# Pyr0-Piezo_Direct_Extruder_Board2_1_2.net
KiCad netlist of a schematic drawn in EAGLE
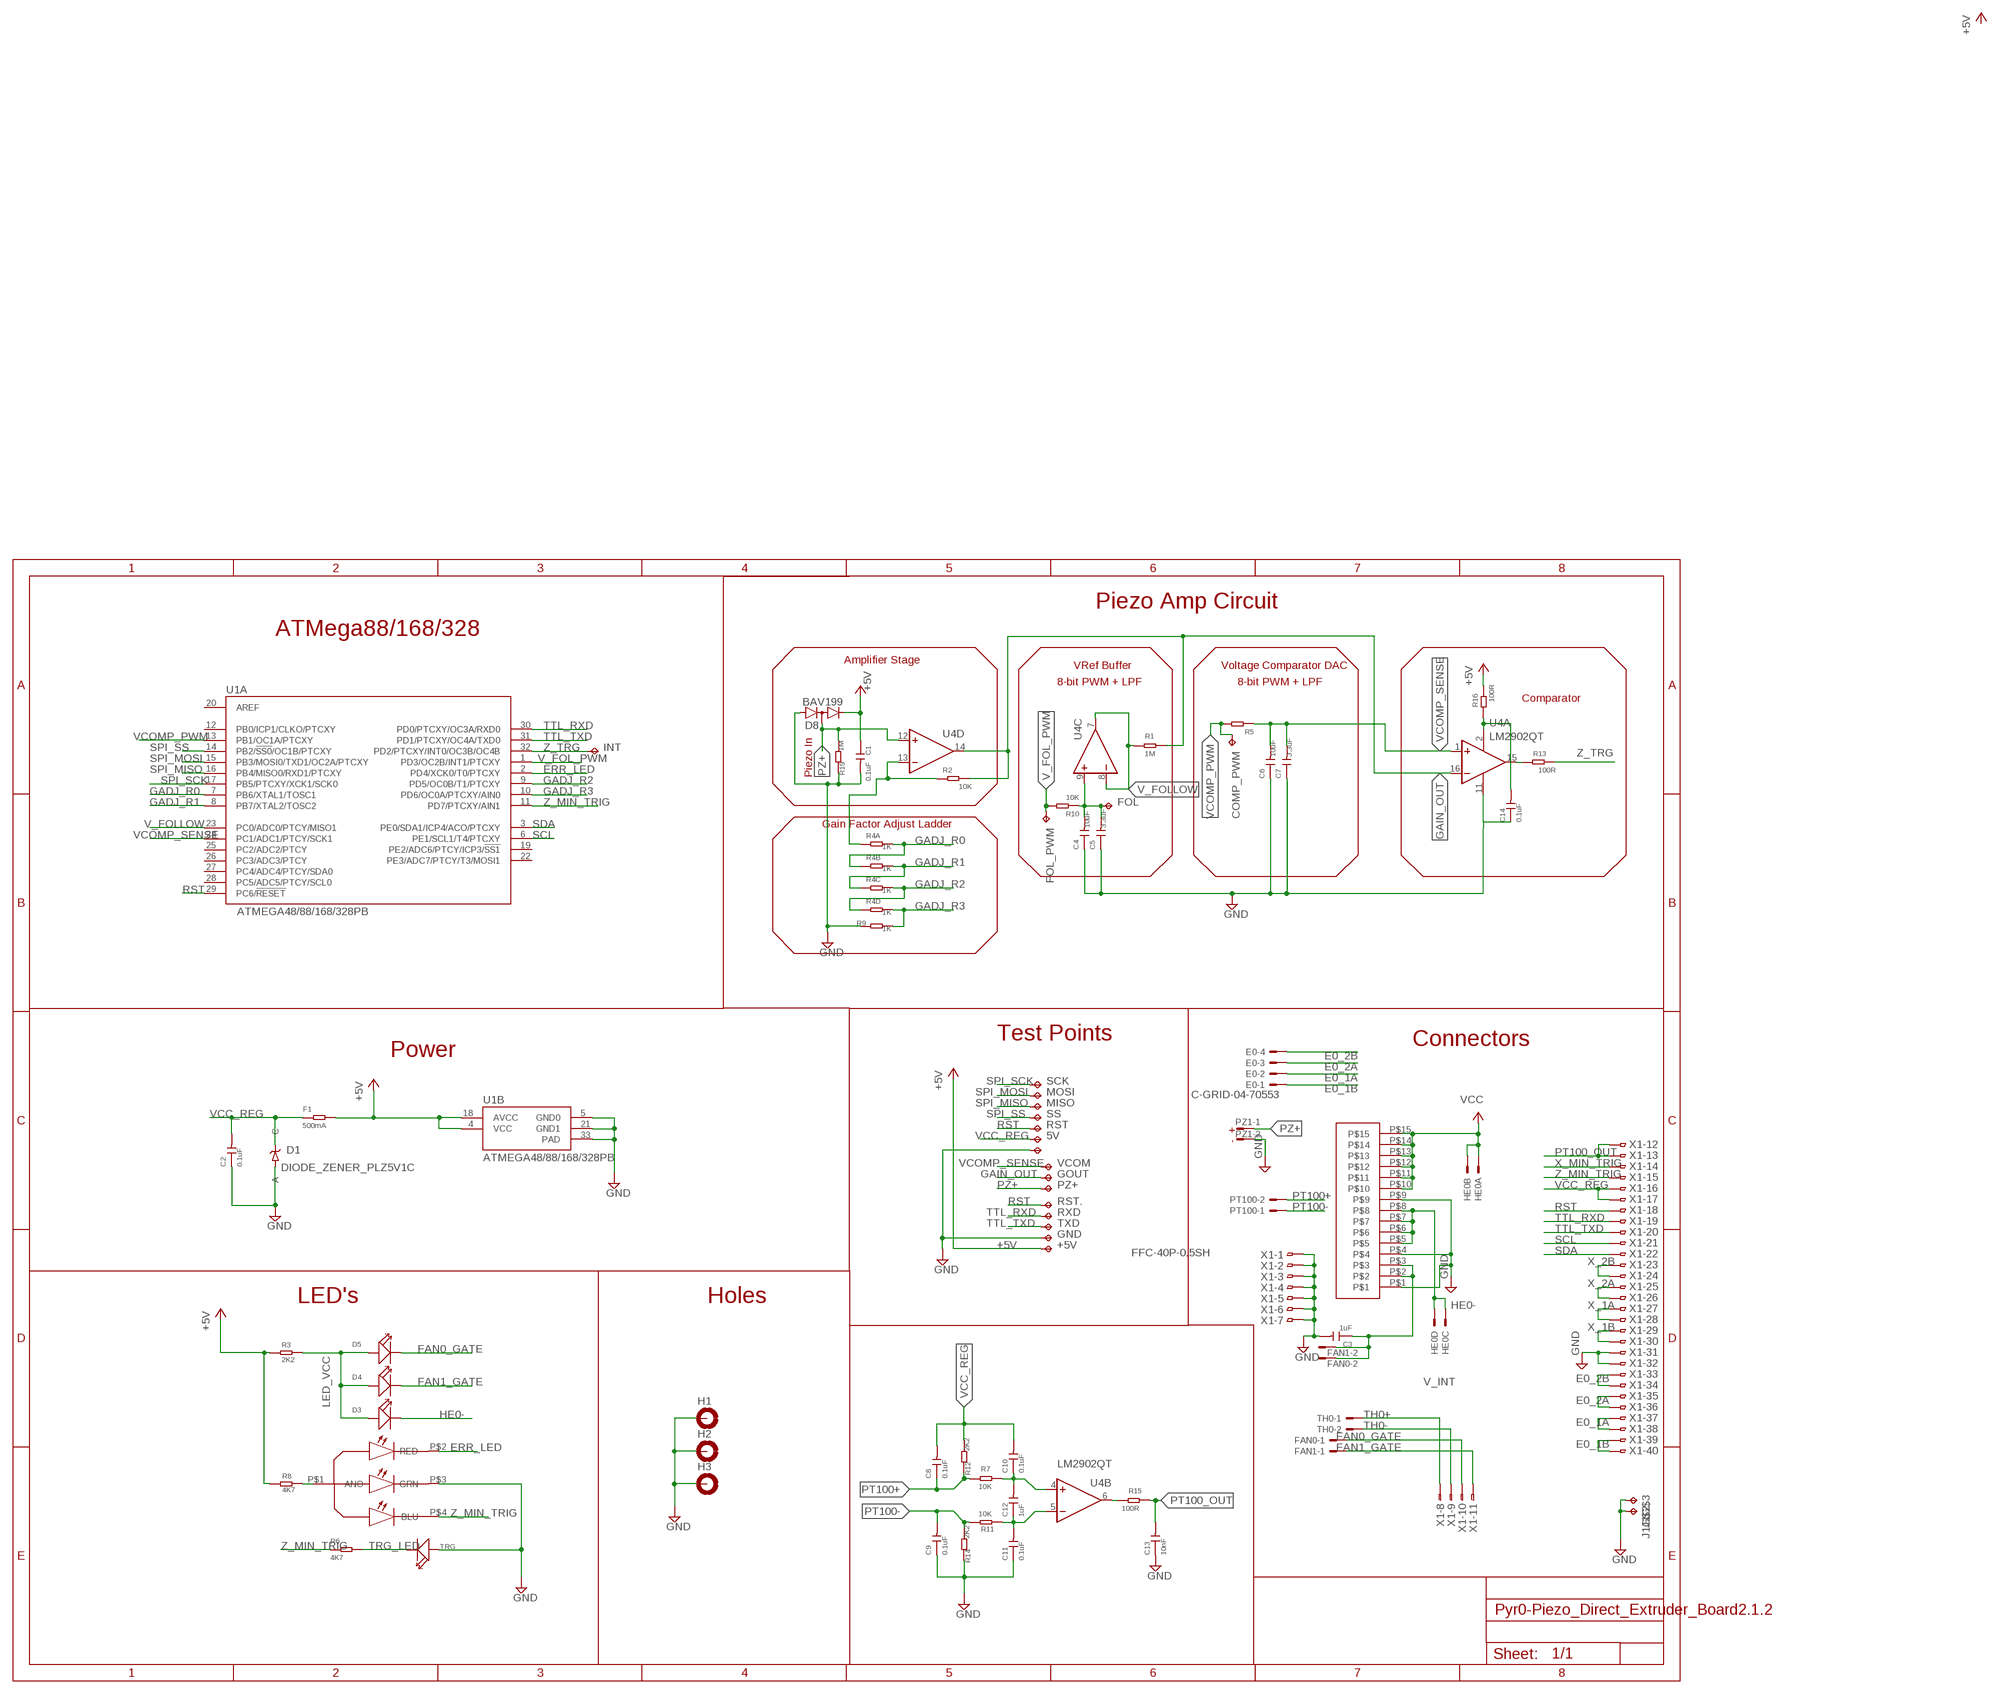
[diagram p0: schematic, sheet 1]

(export (version "E")
  (design (tool "Eeschema 10.0.6"))
  (components
    (comp (ref "+5V")
      (value "TPTP13SQ")
      (footprint "eagle-import:TP13SQ")
      (libsource (lib "eagle-import") (part "testpad_385_TPTP13SQ"))
    )
    (comp (ref "5V")
      (value "TPTP13SQ")
      (footprint "eagle-import:TP13SQ")
      (libsource (lib "eagle-import") (part "TPTP13SQ"))
    )
    (comp (ref "C1")
      (value "0.1uF")
      (footprint "eagle-import:CAPC2012X130")
      (libsource (lib "eagle-import") (part "SEEED-CAPACITOR_CERAMIC-10UF-25V-10%-X5R(0805)CAP_0805-3D"))
    )
    (comp (ref "C2")
      (value "0.1uF")
      (footprint "eagle-import:CAPC1005X50")
      (libsource (lib "eagle-import") (part "CERAMIC-1NF-50V-10%-X7R(0402)CAP_0402"))
    )
    (comp (ref "C3")
      (value "1uF")
      (footprint "eagle-import:CAPC1609X80")
      (libsource (lib "eagle-import") (part "SEEED-CAPACITOR_CERAMIC-10UF-25V-10%-X5R(0805)CAP_0603_GEN"))
    )
    (comp (ref "C4")
      (value "10uF")
      (footprint "eagle-import:CAPC1005X50")
      (libsource (lib "eagle-import") (part "CERAMIC-1NF-50V-10%-X7R(0402)CAP_0402"))
    )
    (comp (ref "C5")
      (value "3.3uF")
      (footprint "eagle-import:CAPC1609X80")
      (libsource (lib "eagle-import") (part "SEEED-CAPACITOR_CERAMIC-10UF-25V-10%-X5R(0805)CAP_0603_GEN"))
    )
    (comp (ref "C6")
      (value "10uF")
      (footprint "eagle-import:CAPC1005X50")
      (libsource (lib "eagle-import") (part "CERAMIC-1NF-50V-10%-X7R(0402)CAP_0402"))
    )
    (comp (ref "C7")
      (value "3.3uF")
      (footprint "eagle-import:CAPC1609X80")
      (libsource (lib "eagle-import") (part "SEEED-CAPACITOR_CERAMIC-10UF-25V-10%-X5R(0805)CAP_0603_GEN"))
    )
    (comp (ref "C8")
      (value "0.1uF")
      (footprint "eagle-import:CAPC1005X50")
      (libsource (lib "eagle-import") (part "CERAMIC-1NF-50V-10%-X7R(0402)CAP_0402"))
    )
    (comp (ref "C9")
      (value "0.1uF")
      (footprint "eagle-import:CAPC1005X50")
      (libsource (lib "eagle-import") (part "CERAMIC-1NF-50V-10%-X7R(0402)CAP_0402"))
    )
    (comp (ref "C10")
      (value "0.1uF")
      (footprint "eagle-import:CAPC1005X50")
      (libsource (lib "eagle-import") (part "CERAMIC-1NF-50V-10%-X7R(0402)CAP_0402"))
    )
    (comp (ref "C11")
      (value "0.1uF")
      (footprint "eagle-import:CAPC1005X50")
      (libsource (lib "eagle-import") (part "CERAMIC-1NF-50V-10%-X7R(0402)CAP_0402"))
    )
    (comp (ref "C12")
      (value "1uF")
      (footprint "eagle-import:CAPC1005X50")
      (libsource (lib "eagle-import") (part "CERAMIC-1NF-50V-10%-X7R(0402)CAP_0402"))
    )
    (comp (ref "C13")
      (value "10nF")
      (footprint "eagle-import:CAPC1005X50")
      (libsource (lib "eagle-import") (part "CERAMIC-1NF-50V-10%-X7R(0402)CAP_0402"))
    )
    (comp (ref "C14")
      (value "0.1uF")
      (footprint "eagle-import:CAPC1005X50")
      (libsource (lib "eagle-import") (part "CERAMIC-1NF-50V-10%-X7R(0402)CAP_0402"))
    )
    (comp (ref "COMP_PWM")
      (value "TPTP09R")
      (footprint "eagle-import:TP09R")
      (libsource (lib "eagle-import") (part "TPTP09R"))
    )
    (comp (ref "D1")
      (value "DIODE_ZENER_PLZ5V1C")
      (footprint "eagle-import:DO-219AC")
      (libsource (lib "eagle-import") (part "DIODE_ZENER_PLZ5V1C"))
    )
    (comp (ref "D2")
      (value "LED-RGB-COM_ANO4PLCC")
      (footprint "eagle-import:4PLCC")
      (libsource (lib "eagle-import") (part "LED-RGB-COM_ANO4PLCC"))
    )
    (comp (ref "D3")
      (value "SEEED-LED_SMD-LED-CLEAR-BLUE(0603)LED_0603")
      (footprint "eagle-import:SEEED-LED_LED-0603")
      (libsource (lib "eagle-import") (part "SEEED-LED_SMD-LED-CLEAR-BLUE(0603)LED_0603"))
    )
    (comp (ref "D4")
      (value "SEEED-LED_SMD-LED-CLEAR-BLUE(0603)LED_0603")
      (footprint "eagle-import:SEEED-LED_LED-0603")
      (libsource (lib "eagle-import") (part "SEEED-LED_SMD-LED-CLEAR-BLUE(0603)LED_0603"))
    )
    (comp (ref "D5")
      (value "SEEED-LED_SMD-LED-CLEAR-BLUE(0603)LED_0603")
      (footprint "eagle-import:SEEED-LED_LED-0603")
      (libsource (lib "eagle-import") (part "SEEED-LED_SMD-LED-CLEAR-BLUE(0603)LED_0603"))
    )
    (comp (ref "D8")
      (value "BAV199")
      (footprint "eagle-import:SOT23")
      (libsource (lib "eagle-import") (part "BAV199"))
    )
    (comp (ref "E0")
      (value "C-GRID-04-70553")
      (footprint "eagle-import:70553-04")
      (fields (field (name "MF") "MOLEX"))
      (libsource (lib "eagle-import") (part "C-GRID-04-70553"))
    )
    (comp (ref "F1")
      (value "500mA")
      (footprint "eagle-import:SEEED-RESISTOR_R0603")
      (libsource (lib "eagle-import") (part "SEEED-RESISTOR_SMD-RES-1.5K-1%-1/10W(0603)DETAILED_MODEL"))
    )
    (comp (ref "FAN0")
      (value "CON-MOLEX-2P-1.27MM048")
      (footprint "eagle-import:53048-02")
      (fields (field (name "MF") "MOLEX") (field (name "MPN") "53048-0210"))
      (libsource (lib "eagle-import") (part "CON-MOLEX-2P-1.27MM048"))
    )
    (comp (ref "FAN1")
      (value "CON-MOLEX-2P-1.27MM048")
      (footprint "eagle-import:53048-02")
      (fields (field (name "MF") "MOLEX") (field (name "MPN") "53048-0210"))
      (libsource (lib "eagle-import") (part "CON-MOLEX-2P-1.27MM048"))
    )
    (comp (ref "FOL")
      (value "TPTP13SQ")
      (footprint "eagle-import:TP13SQ")
      (libsource (lib "eagle-import") (part "TPTP13SQ"))
    )
    (comp (ref "FOL_PWM")
      (value "TPTP09R")
      (footprint "eagle-import:TP09R")
      (libsource (lib "eagle-import") (part "TPTP09R"))
    )
    (comp (ref "GND")
      (value "TPTP13SQ")
      (footprint "eagle-import:TP13SQ")
      (libsource (lib "eagle-import") (part "testpad_385_TPTP13SQ"))
    )
    (comp (ref "GOUT")
      (value "TPTP13SQ")
      (footprint "eagle-import:TP13SQ")
      (libsource (lib "eagle-import") (part "TPTP13SQ"))
    )
    (comp (ref "H1")
      (value "HOLES_MOUNT-PAD-ROUND3.2")
      (footprint "eagle-import:HOLES_3,2-PAD")
      (libsource (lib "eagle-import") (part "HOLES_MOUNT-PAD-ROUND3.2"))
    )
    (comp (ref "H2")
      (value "HOLES_MOUNT-PAD-ROUND3.2")
      (footprint "eagle-import:HOLES_3,2-PAD")
      (libsource (lib "eagle-import") (part "HOLES_MOUNT-PAD-ROUND3.2"))
    )
    (comp (ref "H3")
      (value "HOLES_MOUNT-PAD-ROUND3.2")
      (footprint "eagle-import:HOLES_3,2-PAD")
      (libsource (lib "eagle-import") (part "HOLES_MOUNT-PAD-ROUND3.2"))
    )
    (comp (ref "HE0")
      (value "JST-2.54-2X2JST-DUPONT-2.54-2X2")
      (footprint "eagle-import:HDRRAR4W64P254_2X2_556X736X556B")
      (libsource (lib "eagle-import") (part "JST-2.54-2X2JST-DUPONT-2.54-2X2"))
    )
    (comp (ref "INT")
      (value "TPTP13R")
      (footprint "eagle-import:TP13R")
      (libsource (lib "eagle-import") (part "TPTP13R"))
    )
    (comp (ref "J1")
      (value "FFC-15P-1MM")
      (footprint "eagle-import:FFC-15P-1MM")
      (libsource (lib "eagle-import") (part "FFC-15P-1MM"))
    )
    (comp (ref "MISO")
      (value "TPTP13SQ")
      (footprint "eagle-import:TP13SQ")
      (libsource (lib "eagle-import") (part "TPTP13SQ"))
    )
    (comp (ref "MOSI")
      (value "TPTP13SQ")
      (footprint "eagle-import:TP13SQ")
      (libsource (lib "eagle-import") (part "TPTP13SQ"))
    )
    (comp (ref "PT100")
      (value "CON-MOLEX-2P-1.27MM048")
      (footprint "eagle-import:53048-02")
      (fields (field (name "MF") "MOLEX") (field (name "MPN") "53048-0210"))
      (libsource (lib "eagle-import") (part "CON-MOLEX-2P-1.27MM048"))
    )
    (comp (ref "PZ+")
      (value "TPTP13SQ")
      (footprint "eagle-import:TP13SQ")
      (libsource (lib "eagle-import") (part "TPTP13SQ"))
    )
    (comp (ref "PZ1")
      (value "CON-MOLEX-2P-1.27MM048")
      (footprint "eagle-import:53048-02")
      (fields (field (name "MF") "MOLEX") (field (name "MPN") "53048-0210"))
      (libsource (lib "eagle-import") (part "CON-MOLEX-2P-1.27MM048"))
    )
    (comp (ref "R1")
      (value "1M")
      (footprint "eagle-import:R0402")
      (fields (field (name "MPN") "RC0402JR-070RL"))
      (libsource (lib "eagle-import") (part "SMD-RES-0R-5%-1/16W(0402)"))
    )
    (comp (ref "R2")
      (value "10K")
      (footprint "eagle-import:R0402")
      (fields (field (name "MPN") "RC0402JR-070RL"))
      (libsource (lib "eagle-import") (part "SMD-RES-0R-5%-1/16W(0402)"))
    )
    (comp (ref "R3")
      (value "2K2")
      (footprint "eagle-import:R0402")
      (fields (field (name "MPN") "RC0402JR-070RL"))
      (libsource (lib "eagle-import") (part "SMD-RES-0R-5%-1/16W(0402)"))
    )
    (comp (ref "R4")
      (value "1K")
      (footprint "eagle-import:EXBN8V")
      (libsource (lib "eagle-import") (part "RESISTOR_NETWORK_X40804"))
    )
    (comp (ref "R5")
      (value "0R")
      (footprint "eagle-import:R0402")
      (fields (field (name "MPN") "RC0402JR-070RL"))
      (libsource (lib "eagle-import") (part "SMD-RES-0R-5%-1/16W(0402)"))
    )
    (comp (ref "R6")
      (value "4K7")
      (footprint "eagle-import:R0402")
      (fields (field (name "MPN") "RC0402JR-070RL"))
      (libsource (lib "eagle-import") (part "SMD-RES-0R-5%-1/16W(0402)"))
    )
    (comp (ref "R7")
      (value "10K")
      (footprint "eagle-import:R0402")
      (fields (field (name "MPN") "RC0402JR-070RL"))
      (libsource (lib "eagle-import") (part "SMD-RES-0R-5%-1/16W(0402)"))
    )
    (comp (ref "R8")
      (value "4K7")
      (footprint "eagle-import:R0402")
      (fields (field (name "MPN") "RC0402JR-070RL"))
      (libsource (lib "eagle-import") (part "SMD-RES-0R-5%-1/16W(0402)"))
    )
    (comp (ref "R9")
      (value "1K")
      (footprint "eagle-import:R0402")
      (fields (field (name "MPN") "RC0402JR-070RL"))
      (libsource (lib "eagle-import") (part "SMD-RES-0R-5%-1/16W(0402)"))
    )
    (comp (ref "R10")
      (value "10K")
      (footprint "eagle-import:R0402")
      (fields (field (name "MPN") "RC0402JR-070RL"))
      (libsource (lib "eagle-import") (part "SMD-RES-0R-5%-1/16W(0402)"))
    )
    (comp (ref "R11")
      (value "10K")
      (footprint "eagle-import:R0402")
      (fields (field (name "MPN") "RC0402JR-070RL"))
      (libsource (lib "eagle-import") (part "SMD-RES-0R-5%-1/16W(0402)"))
    )
    (comp (ref "R12")
      (value "2K2")
      (footprint "eagle-import:R0402")
      (fields (field (name "MPN") "RC0402JR-070RL"))
      (libsource (lib "eagle-import") (part "SMD-RES-0R-5%-1/16W(0402)"))
    )
    (comp (ref "R13")
      (value "100R")
      (footprint "eagle-import:R0402")
      (fields (field (name "MPN") "RC0402JR-070RL"))
      (libsource (lib "eagle-import") (part "SMD-RES-0R-5%-1/16W(0402)"))
    )
    (comp (ref "R14")
      (value "2K2")
      (footprint "eagle-import:R0402")
      (fields (field (name "MPN") "RC0402JR-070RL"))
      (libsource (lib "eagle-import") (part "SMD-RES-0R-5%-1/16W(0402)"))
    )
    (comp (ref "R15")
      (value "100R")
      (footprint "eagle-import:R0402")
      (fields (field (name "MPN") "RC0402JR-070RL"))
      (libsource (lib "eagle-import") (part "SMD-RES-0R-5%-1/16W(0402)"))
    )
    (comp (ref "R16")
      (value "100R")
      (footprint "eagle-import:R0402")
      (fields (field (name "MPN") "RC0402JR-070RL"))
      (libsource (lib "eagle-import") (part "SMD-RES-0R-5%-1/16W(0402)"))
    )
    (comp (ref "R19")
      (value "1M")
      (footprint "eagle-import:R0402")
      (fields (field (name "MPN") "RC0402JR-070RL"))
      (libsource (lib "eagle-import") (part "SMD-RES-0R-5%-1/16W(0402)"))
    )
    (comp (ref "RST")
      (value "TPTP13SQ")
      (footprint "eagle-import:TP13SQ")
      (libsource (lib "eagle-import") (part "TPTP13SQ"))
    )
    (comp (ref "RST.")
      (value "TPTP13SQ")
      (footprint "eagle-import:TP13SQ")
      (libsource (lib "eagle-import") (part "testpad_385_TPTP13SQ"))
    )
    (comp (ref "RXD")
      (value "TPTP13SQ")
      (footprint "eagle-import:TP13SQ")
      (libsource (lib "eagle-import") (part "testpad_385_TPTP13SQ"))
    )
    (comp (ref "SCK")
      (value "TPTP13SQ")
      (footprint "eagle-import:TP13SQ")
      (libsource (lib "eagle-import") (part "TPTP13SQ"))
    )
    (comp (ref "SS")
      (value "TPTP06R")
      (footprint "eagle-import:TP06R")
      (libsource (lib "eagle-import") (part "testpad_385_TPTP06R"))
    )
    (comp (ref "TH0")
      (value "CON-MOLEX-2P-1.27MM048")
      (footprint "eagle-import:53048-02")
      (fields (field (name "MF") "MOLEX") (field (name "MPN") "53048-0210"))
      (libsource (lib "eagle-import") (part "CON-MOLEX-2P-1.27MM048"))
    )
    (comp (ref "TRG")
      (value "SEEED-LED_SMD-LED-CLEAR-BLUE(0603)LED_0603")
      (footprint "eagle-import:SEEED-LED_LED-0603")
      (libsource (lib "eagle-import") (part "SEEED-LED_SMD-LED-CLEAR-BLUE(0603)LED_0603"))
    )
    (comp (ref "TXD")
      (value "TPTP13SQ")
      (footprint "eagle-import:TP13SQ")
      (libsource (lib "eagle-import") (part "testpad_385_TPTP13SQ"))
    )
    (comp (ref "U1")
      (value "ATMEGA48/88/168/328PB")
      (footprint "eagle-import:QFN50P500X500X90-33N")
      (fields (field (name "MF") "Microchip") (field (name "MP") "ATMEGA328PB-MU"))
      (libsource (lib "eagle-import") (part "ATMEGA48/88/168/328PB"))
    )
    (comp (ref "U4")
      (value "LM2902QT")
      (footprint "eagle-import:QFN16")
      (libsource (lib "eagle-import") (part "LM2902QT"))
    )
    (comp (ref "VCOM")
      (value "TPTP13SQ")
      (footprint "eagle-import:TP13SQ")
      (libsource (lib "eagle-import") (part "TPTP13SQ"))
    )
    (comp (ref "X1")
      (value "FFC-40P-0.5SH")
      (footprint "eagle-import:FH12-40S-0.5SH")
      (fields (field (name "MPN") "FH12-40S-0.5SH(55)"))
      (libsource (lib "eagle-import") (part "FFC-40P-0.5SH"))
    )
    (comp (ref "⏚")
      (value "TPTP13SQ")
      (footprint "eagle-import:TP13SQ")
      (libsource (lib "eagle-import") (part "testpad_385_TPTP13SQ"))
    )
  )
  (nets
    (net (code "1") (name "+5V") (class "Default")
      (node (ref "+5V") (pin "TP") (pinfunction "TP_TP") (pintype "input"))
      (node (ref "C1") (pin "1") (pinfunction "1_1") (pintype "passive"))
      (node (ref "D8") (pin "2") (pinfunction "C_2") (pintype "passive"))
      (node (ref "F1") (pin "2") (pinfunction "2_2") (pintype "passive"))
      (node (ref "R16") (pin "2") (pinfunction "2_2") (pintype "passive"))
      (node (ref "R3") (pin "1") (pinfunction "1_1") (pintype "passive"))
      (node (ref "R8") (pin "1") (pinfunction "1_1") (pintype "passive"))
      (node (ref "U1") (pin "18") (pinfunction "AVCC_18") (pintype "power_in"))
      (node (ref "U1") (pin "4") (pinfunction "VCC_4") (pintype "power_in"))
    )
    (net (code "2") (name "/E0_1A") (class "Default")
      (node (ref "E0") (pin "2") (pinfunction "S_2") (pintype "passive"))
      (node (ref "X1") (pin "37") (pinfunction "1_37") (pintype "passive"))
      (node (ref "X1") (pin "38") (pinfunction "1_38") (pintype "passive"))
    )
    (net (code "3") (name "/E0_1B") (class "Default")
      (node (ref "E0") (pin "1") (pinfunction "S_1") (pintype "passive"))
      (node (ref "X1") (pin "39") (pinfunction "1_39") (pintype "passive"))
      (node (ref "X1") (pin "40") (pinfunction "1_40") (pintype "passive"))
    )
    (net (code "4") (name "/E0_2A") (class "Default")
      (node (ref "E0") (pin "3") (pinfunction "S_3") (pintype "passive"))
      (node (ref "X1") (pin "35") (pinfunction "1_35") (pintype "passive"))
      (node (ref "X1") (pin "36") (pinfunction "1_36") (pintype "passive"))
    )
    (net (code "5") (name "/E0_2B") (class "Default")
      (node (ref "E0") (pin "4") (pinfunction "S_4") (pintype "passive"))
      (node (ref "X1") (pin "33") (pinfunction "1_33") (pintype "passive"))
      (node (ref "X1") (pin "34") (pinfunction "1_34") (pintype "passive"))
    )
    (net (code "6") (name "/ERR_LED") (class "Default")
      (node (ref "D2") (pin "P$2") (pinfunction "RED_P$2") (pintype "bidirectional"))
      (node (ref "U1") (pin "2") (pinfunction "PD4/XCK0/T0/PTCXY_2") (pintype "bidirectional"))
    )
    (net (code "7") (name "/FAN0_GATE") (class "Default")
      (node (ref "D5") (pin "-") (pinfunction "-_-") (pintype "passive"))
      (node (ref "FAN0") (pin "1") (pinfunction "S_1") (pintype "passive"))
      (node (ref "X1") (pin "10") (pinfunction "1_10") (pintype "passive"))
    )
    (net (code "8") (name "/FAN1_GATE") (class "Default")
      (node (ref "D4") (pin "-") (pinfunction "-_-") (pintype "passive"))
      (node (ref "FAN1") (pin "1") (pinfunction "S_1") (pintype "passive"))
      (node (ref "X1") (pin "11") (pinfunction "1_11") (pintype "passive"))
    )
    (net (code "9") (name "/GADJ_R0") (class "Default")
      (node (ref "R4") (pin "2") (pinfunction "1_2") (pintype "passive"))
      (node (ref "R4") (pin "8") (pinfunction "2_8") (pintype "passive"))
      (node (ref "U1") (pin "7") (pinfunction "PB6/XTAL1/TOSC1_7") (pintype "bidirectional"))
    )
    (net (code "10") (name "/GADJ_R1") (class "Default")
      (node (ref "R4") (pin "3") (pinfunction "1_3") (pintype "passive"))
      (node (ref "R4") (pin "7") (pinfunction "2_7") (pintype "passive"))
      (node (ref "U1") (pin "8") (pinfunction "PB7/XTAL2/TOSC2_8") (pintype "bidirectional"))
    )
    (net (code "11") (name "/GADJ_R2") (class "Default")
      (node (ref "R4") (pin "4") (pinfunction "1_4") (pintype "passive"))
      (node (ref "R4") (pin "6") (pinfunction "2_6") (pintype "passive"))
      (node (ref "U1") (pin "9") (pinfunction "PD5/OC0B/T1/PTCXY_9") (pintype "bidirectional"))
    )
    (net (code "12") (name "/GADJ_R3") (class "Default")
      (node (ref "R4") (pin "5") (pinfunction "2_5") (pintype "passive"))
      (node (ref "R9") (pin "2") (pinfunction "2_2") (pintype "passive"))
      (node (ref "U1") (pin "10") (pinfunction "PD6/OC0A/PTCXY/AIN0_10") (pintype "bidirectional"))
    )
    (net (code "13") (name "/HE0-") (class "Default")
      (node (ref "D3") (pin "-") (pinfunction "-_-") (pintype "passive"))
      (node (ref "HE0") (pin "3") (pinfunction "S_3") (pintype "passive"))
      (node (ref "HE0") (pin "4") (pinfunction "S_4") (pintype "passive"))
      (node (ref "J1") (pin "P$5") (pinfunction "P$5_P$5") (pintype "bidirectional"))
      (node (ref "J1") (pin "P$6") (pinfunction "P$6_P$6") (pintype "bidirectional"))
      (node (ref "J1") (pin "P$7") (pinfunction "P$7_P$7") (pintype "bidirectional"))
      (node (ref "J1") (pin "P$8") (pinfunction "P$8_P$8") (pintype "bidirectional"))
    )
    (net (code "14") (name "/LED_VCC") (class "Default")
      (node (ref "D3") (pin "+") (pinfunction "+_+") (pintype "passive"))
      (node (ref "D4") (pin "+") (pinfunction "+_+") (pintype "passive"))
      (node (ref "D5") (pin "+") (pinfunction "+_+") (pintype "passive"))
      (node (ref "R3") (pin "2") (pinfunction "2_2") (pintype "passive"))
    )
    (net (code "15") (name "/RST") (class "Default")
      (node (ref "RST") (pin "TP") (pinfunction "TP_TP") (pintype "input"))
      (node (ref "RST.") (pin "TP") (pinfunction "TP_TP") (pintype "input"))
      (node (ref "U1") (pin "29") (pinfunction "PC6/~{RESET}_29") (pintype "bidirectional"))
      (node (ref "X1") (pin "18") (pinfunction "1_18") (pintype "passive"))
    )
    (net (code "16") (name "/SCL") (class "Default")
      (node (ref "U1") (pin "6") (pinfunction "PE1/SCL1/T4/PTCXY_6") (pintype "bidirectional"))
      (node (ref "X1") (pin "21") (pinfunction "1_21") (pintype "passive"))
    )
    (net (code "17") (name "/SDA") (class "Default")
      (node (ref "U1") (pin "3") (pinfunction "PE0/SDA1/ICP4/ACO/PTCXY_3") (pintype "bidirectional"))
      (node (ref "X1") (pin "22") (pinfunction "1_22") (pintype "passive"))
    )
    (net (code "18") (name "/SPI_MISO") (class "Default")
      (node (ref "MISO") (pin "TP") (pinfunction "TP_TP") (pintype "input"))
      (node (ref "U1") (pin "16") (pinfunction "PB4/MISO0/RXD1/PTCXY_16") (pintype "bidirectional"))
    )
    (net (code "19") (name "/SPI_MOSI") (class "Default")
      (node (ref "MOSI") (pin "TP") (pinfunction "TP_TP") (pintype "input"))
      (node (ref "U1") (pin "15") (pinfunction "PB3/MOSI0/TXD1/OC2A/PTCXY_15") (pintype "bidirectional"))
    )
    (net (code "20") (name "/SPI_SCK") (class "Default")
      (node (ref "SCK") (pin "TP") (pinfunction "TP_TP") (pintype "input"))
      (node (ref "U1") (pin "17") (pinfunction "PB5/PTCXY/XCK1/SCK0_17") (pintype "bidirectional"))
    )
    (net (code "21") (name "/SPI_SS") (class "Default")
      (node (ref "SS") (pin "TP") (pinfunction "TP_TP") (pintype "input"))
      (node (ref "U1") (pin "14") (pinfunction "PB2/~{SS0}/OC1B/PTCXY_14") (pintype "bidirectional"))
    )
    (net (code "22") (name "/TH0+") (class "Default")
      (node (ref "TH0") (pin "1") (pinfunction "S_1") (pintype "passive"))
      (node (ref "X1") (pin "8") (pinfunction "1_8") (pintype "passive"))
    )
    (net (code "23") (name "/TH0-") (class "Default")
      (node (ref "TH0") (pin "2") (pinfunction "S_2") (pintype "passive"))
      (node (ref "X1") (pin "9") (pinfunction "1_9") (pintype "passive"))
    )
    (net (code "24") (name "/TRG_LED") (class "Default")
      (node (ref "R6") (pin "2") (pinfunction "2_2") (pintype "passive"))
      (node (ref "TRG") (pin "-") (pinfunction "-_-") (pintype "passive"))
    )
    (net (code "25") (name "/TTL_RXD") (class "Default")
      (node (ref "RXD") (pin "TP") (pinfunction "TP_TP") (pintype "input"))
      (node (ref "U1") (pin "30") (pinfunction "PD0/PTCXY/OC3A/RXD0_30") (pintype "bidirectional"))
      (node (ref "X1") (pin "19") (pinfunction "1_19") (pintype "passive"))
    )
    (net (code "26") (name "/TTL_TXD") (class "Default")
      (node (ref "TXD") (pin "TP") (pinfunction "TP_TP") (pintype "input"))
      (node (ref "U1") (pin "31") (pinfunction "PD1/PTCXY/OC4A/TXD0_31") (pintype "bidirectional"))
      (node (ref "X1") (pin "20") (pinfunction "1_20") (pintype "passive"))
    )
    (net (code "27") (name "/V_INT") (class "Default")
      (node (ref "C3") (pin "1") (pinfunction "1_1") (pintype "passive"))
      (node (ref "FAN0") (pin "2") (pinfunction "S_2") (pintype "passive"))
      (node (ref "FAN1") (pin "2") (pinfunction "S_2") (pintype "passive"))
      (node (ref "J1") (pin "P$2") (pinfunction "P$2_P$2") (pintype "bidirectional"))
      (node (ref "J1") (pin "P$3") (pinfunction "P$3_P$3") (pintype "bidirectional"))
    )
    (net (code "28") (name "/X_1A") (class "Default")
      (node (ref "X1") (pin "27") (pinfunction "1_27") (pintype "passive"))
      (node (ref "X1") (pin "28") (pinfunction "1_28") (pintype "passive"))
    )
    (net (code "29") (name "/X_1B") (class "Default")
      (node (ref "X1") (pin "29") (pinfunction "1_29") (pintype "passive"))
      (node (ref "X1") (pin "30") (pinfunction "1_30") (pintype "passive"))
    )
    (net (code "30") (name "/X_2A") (class "Default")
      (node (ref "X1") (pin "25") (pinfunction "1_25") (pintype "passive"))
      (node (ref "X1") (pin "26") (pinfunction "1_26") (pintype "passive"))
    )
    (net (code "31") (name "/X_2B") (class "Default")
      (node (ref "X1") (pin "23") (pinfunction "1_23") (pintype "passive"))
      (node (ref "X1") (pin "24") (pinfunction "1_24") (pintype "passive"))
    )
    (net (code "32") (name "/X_MIN_TRIG") (class "Default")
      (node (ref "X1") (pin "14") (pinfunction "1_14") (pintype "passive"))
    )
    (net (code "33") (name "/Z_MIN_TRIG") (class "Default")
      (node (ref "D2") (pin "P$4") (pinfunction "BLU_P$4") (pintype "bidirectional"))
      (node (ref "R6") (pin "1") (pinfunction "1_1") (pintype "passive"))
      (node (ref "U1") (pin "11") (pinfunction "PD7/PTCXY/AIN1_11") (pintype "bidirectional"))
      (node (ref "X1") (pin "15") (pinfunction "1_15") (pintype "passive"))
    )
    (net (code "34") (name "/Z_TRG") (class "Default")
      (node (ref "INT") (pin "TP") (pinfunction "TP_TP") (pintype "input"))
      (node (ref "R13") (pin "2") (pinfunction "2_2") (pintype "passive"))
      (node (ref "U1") (pin "32") (pinfunction "PD2/PTCXY/INT0/OC3B/OC4B_32") (pintype "bidirectional"))
    )
    (net (code "35") (name "GAIN_OUT") (class "Default")
      (node (ref "GOUT") (pin "TP") (pinfunction "TP_TP") (pintype "input"))
      (node (ref "R1") (pin "2") (pinfunction "2_2") (pintype "passive"))
      (node (ref "R2") (pin "2") (pinfunction "2_2") (pintype "passive"))
      (node (ref "U4") (pin "14") (pinfunction "OUT_14") (pintype "output"))
      (node (ref "U4") (pin "16") (pinfunction "-IN_16") (pintype "input"))
    )
    (net (code "36") (name "GND") (class "Default")
      (node (ref "C1") (pin "2") (pinfunction "2_2") (pintype "passive"))
      (node (ref "C11") (pin "1") (pinfunction "1_1") (pintype "passive"))
      (node (ref "C13") (pin "1") (pinfunction "1_1") (pintype "passive"))
      (node (ref "C14") (pin "1") (pinfunction "1_1") (pintype "passive"))
      (node (ref "C2") (pin "1") (pinfunction "1_1") (pintype "passive"))
      (node (ref "C3") (pin "2") (pinfunction "2_2") (pintype "passive"))
      (node (ref "C4") (pin "1") (pinfunction "1_1") (pintype "passive"))
      (node (ref "C5") (pin "1") (pinfunction "1_1") (pintype "passive"))
      (node (ref "C6") (pin "1") (pinfunction "1_1") (pintype "passive"))
      (node (ref "C7") (pin "1") (pinfunction "1_1") (pintype "passive"))
      (node (ref "C9") (pin "1") (pinfunction "1_1") (pintype "passive"))
      (node (ref "D1") (pin "P$1") (pinfunction "A_P$1") (pintype "passive"))
      (node (ref "D2") (pin "P$3") (pinfunction "GRN_P$3") (pintype "bidirectional"))
      (node (ref "D8") (pin "1") (pinfunction "A_1") (pintype "passive"))
      (node (ref "GND") (pin "TP") (pinfunction "TP_TP") (pintype "input"))
      (node (ref "H1") (pin "B3,2") (pinfunction "MOUNT_B3,2") (pintype "passive"))
      (node (ref "H2") (pin "B3,2") (pinfunction "MOUNT_B3,2") (pintype "passive"))
      (node (ref "H3") (pin "B3,2") (pinfunction "MOUNT_B3,2") (pintype "passive"))
      (node (ref "J1") (pin "P$1") (pinfunction "P$1_P$1") (pintype "bidirectional"))
      (node (ref "J1") (pin "P$16") (pinfunction "TP_P$16") (pintype "input"))
      (node (ref "J1") (pin "P$17") (pinfunction "TP_P$17") (pintype "input"))
      (node (ref "J1") (pin "P$4") (pinfunction "P$4_P$4") (pintype "bidirectional"))
      (node (ref "J1") (pin "P$9") (pinfunction "P$9_P$9") (pintype "bidirectional"))
      (node (ref "PZ1") (pin "2") (pinfunction "S_2") (pintype "passive"))
      (node (ref "R14") (pin "1") (pinfunction "1_1") (pintype "passive"))
      (node (ref "R19") (pin "1") (pinfunction "1_1") (pintype "passive"))
      (node (ref "R9") (pin "1") (pinfunction "1_1") (pintype "passive"))
      (node (ref "TRG") (pin "+") (pinfunction "+_+") (pintype "passive"))
      (node (ref "U1") (pin "21") (pinfunction "GND1_21") (pintype "power_in"))
      (node (ref "U1") (pin "33") (pinfunction "PAD_33") (pintype "power_in"))
      (node (ref "U1") (pin "5") (pinfunction "GND0_5") (pintype "power_in"))
      (node (ref "U4") (pin "11") (pinfunction "V-_11") (pintype "power_in"))
      (node (ref "X1") (pin "1") (pinfunction "1_1") (pintype "passive"))
      (node (ref "X1") (pin "2") (pinfunction "1_2") (pintype "passive"))
      (node (ref "X1") (pin "3") (pinfunction "1_3") (pintype "passive"))
      (node (ref "X1") (pin "31") (pinfunction "1_31") (pintype "passive"))
      (node (ref "X1") (pin "32") (pinfunction "1_32") (pintype "passive"))
      (node (ref "X1") (pin "4") (pinfunction "1_4") (pintype "passive"))
      (node (ref "X1") (pin "5") (pinfunction "1_5") (pintype "passive"))
      (node (ref "X1") (pin "6") (pinfunction "1_6") (pintype "passive"))
      (node (ref "X1") (pin "7") (pinfunction "1_7") (pintype "passive"))
      (node (ref "⏚") (pin "TP") (pinfunction "TP_TP") (pintype "input"))
    )
    (net (code "37") (name "Net-(D2-ANO)") (class "Default")
      (node (ref "D2") (pin "P$1") (pinfunction "ANO_P$1") (pintype "bidirectional"))
      (node (ref "R8") (pin "2") (pinfunction "2_2") (pintype "passive"))
    )
    (net (code "38") (name "Net-(U4A-OUT)") (class "Default")
      (node (ref "R13") (pin "1") (pinfunction "1_1") (pintype "passive"))
      (node (ref "U4") (pin "15") (pinfunction "OUT_15") (pintype "output"))
    )
    (net (code "39") (name "Net-(U4B-+IN)") (class "Default")
      (node (ref "C10") (pin "1") (pinfunction "1_1") (pintype "passive"))
      (node (ref "C12") (pin "2") (pinfunction "2_2") (pintype "passive"))
      (node (ref "R7") (pin "1") (pinfunction "1_1") (pintype "passive"))
      (node (ref "U4") (pin "4") (pinfunction "+IN_4") (pintype "input"))
    )
    (net (code "40") (name "Net-(U4B--IN)") (class "Default")
      (node (ref "C11") (pin "2") (pinfunction "2_2") (pintype "passive"))
      (node (ref "C12") (pin "1") (pinfunction "1_1") (pintype "passive"))
      (node (ref "R11") (pin "1") (pinfunction "1_1") (pintype "passive"))
      (node (ref "U4") (pin "5") (pinfunction "-IN_5") (pintype "input"))
    )
    (net (code "41") (name "Net-(U4B-OUT)") (class "Default")
      (node (ref "R15") (pin "2") (pinfunction "2_2") (pintype "passive"))
      (node (ref "U4") (pin "6") (pinfunction "OUT_6") (pintype "output"))
    )
    (net (code "42") (name "Net-(U4C-+IN)") (class "Default")
      (node (ref "C4") (pin "2") (pinfunction "2_2") (pintype "passive"))
      (node (ref "C5") (pin "2") (pinfunction "2_2") (pintype "passive"))
      (node (ref "FOL") (pin "TP") (pinfunction "TP_TP") (pintype "input"))
      (node (ref "R10") (pin "1") (pinfunction "1_1") (pintype "passive"))
      (node (ref "U4") (pin "9") (pinfunction "+IN_9") (pintype "input"))
    )
    (net (code "43") (name "Net-(U4D--IN)") (class "Default")
      (node (ref "R2") (pin "1") (pinfunction "1_1") (pintype "passive"))
      (node (ref "R4") (pin "1") (pinfunction "1_1") (pintype "passive"))
      (node (ref "U4") (pin "13") (pinfunction "-IN_13") (pintype "input"))
    )
    (net (code "44") (name "Net-(U4E-V+)") (class "Default")
      (node (ref "C14") (pin "2") (pinfunction "2_2") (pintype "passive"))
      (node (ref "R16") (pin "1") (pinfunction "1_1") (pintype "passive"))
      (node (ref "U4") (pin "2") (pinfunction "V+_2") (pintype "power_in"))
    )
    (net (code "45") (name "PT100+") (class "Default")
      (node (ref "C8") (pin "1") (pinfunction "1_1") (pintype "passive"))
      (node (ref "PT100") (pin "2") (pinfunction "S_2") (pintype "passive"))
      (node (ref "R12") (pin "1") (pinfunction "1_1") (pintype "passive"))
      (node (ref "R7") (pin "2") (pinfunction "2_2") (pintype "passive"))
    )
    (net (code "46") (name "PT100-") (class "Default")
      (node (ref "C9") (pin "2") (pinfunction "2_2") (pintype "passive"))
      (node (ref "PT100") (pin "1") (pinfunction "S_1") (pintype "passive"))
      (node (ref "R11") (pin "2") (pinfunction "2_2") (pintype "passive"))
      (node (ref "R14") (pin "2") (pinfunction "2_2") (pintype "passive"))
    )
    (net (code "47") (name "PT100_OUT") (class "Default")
      (node (ref "C13") (pin "2") (pinfunction "2_2") (pintype "passive"))
      (node (ref "R15") (pin "1") (pinfunction "1_1") (pintype "passive"))
      (node (ref "X1") (pin "12") (pinfunction "1_12") (pintype "passive"))
      (node (ref "X1") (pin "13") (pinfunction "1_13") (pintype "passive"))
    )
    (net (code "48") (name "PZ+") (class "Default")
      (node (ref "D8") (pin "3") (pinfunction "AC_3") (pintype "passive"))
      (node (ref "PZ+") (pin "TP") (pinfunction "TP_TP") (pintype "input"))
      (node (ref "PZ1") (pin "1") (pinfunction "S_1") (pintype "passive"))
      (node (ref "R19") (pin "2") (pinfunction "2_2") (pintype "passive"))
      (node (ref "U4") (pin "12") (pinfunction "+IN_12") (pintype "input"))
    )
    (net (code "49") (name "VCC") (class "Default")
      (node (ref "HE0") (pin "1") (pinfunction "S_1") (pintype "passive"))
      (node (ref "HE0") (pin "2") (pinfunction "S_2") (pintype "passive"))
      (node (ref "J1") (pin "P$10") (pinfunction "P$10_P$10") (pintype "bidirectional"))
      (node (ref "J1") (pin "P$11") (pinfunction "P$11_P$11") (pintype "bidirectional"))
      (node (ref "J1") (pin "P$12") (pinfunction "P$12_P$12") (pintype "bidirectional"))
      (node (ref "J1") (pin "P$13") (pinfunction "P$13_P$13") (pintype "bidirectional"))
      (node (ref "J1") (pin "P$14") (pinfunction "P$14_P$14") (pintype "bidirectional"))
      (node (ref "J1") (pin "P$15") (pinfunction "P$15_P$15") (pintype "bidirectional"))
    )
    (net (code "50") (name "VCC_REG") (class "Default")
      (node (ref "5V") (pin "TP") (pinfunction "TP_TP") (pintype "input"))
      (node (ref "C10") (pin "2") (pinfunction "2_2") (pintype "passive"))
      (node (ref "C2") (pin "2") (pinfunction "2_2") (pintype "passive"))
      (node (ref "C8") (pin "2") (pinfunction "2_2") (pintype "passive"))
      (node (ref "D1") (pin "P$2") (pinfunction "C_P$2") (pintype "passive"))
      (node (ref "F1") (pin "1") (pinfunction "1_1") (pintype "passive"))
      (node (ref "R12") (pin "2") (pinfunction "2_2") (pintype "passive"))
      (node (ref "X1") (pin "16") (pinfunction "1_16") (pintype "passive"))
      (node (ref "X1") (pin "17") (pinfunction "1_17") (pintype "passive"))
    )
    (net (code "51") (name "VCOMP_PWM") (class "Default")
      (node (ref "COMP_PWM") (pin "TP") (pinfunction "TP_TP") (pintype "input"))
      (node (ref "R5") (pin "2") (pinfunction "2_2") (pintype "passive"))
      (node (ref "U1") (pin "13") (pinfunction "PB1/OC1A/PTCXY_13") (pintype "bidirectional"))
    )
    (net (code "52") (name "VCOMP_SENSE") (class "Default")
      (node (ref "C6") (pin "2") (pinfunction "2_2") (pintype "passive"))
      (node (ref "C7") (pin "2") (pinfunction "2_2") (pintype "passive"))
      (node (ref "R5") (pin "1") (pinfunction "1_1") (pintype "passive"))
      (node (ref "U1") (pin "24") (pinfunction "PC1/ADC1/PTCY/SCK1_24") (pintype "bidirectional"))
      (node (ref "U4") (pin "1") (pinfunction "+IN_1") (pintype "input"))
      (node (ref "VCOM") (pin "TP") (pinfunction "TP_TP") (pintype "input"))
    )
    (net (code "53") (name "V_FOLLOW") (class "Default")
      (node (ref "R1") (pin "1") (pinfunction "1_1") (pintype "passive"))
      (node (ref "U1") (pin "23") (pinfunction "PC0/ADC0/PTCY/MISO1_23") (pintype "bidirectional"))
      (node (ref "U4") (pin "7") (pinfunction "OUT_7") (pintype "output"))
      (node (ref "U4") (pin "8") (pinfunction "-IN_8") (pintype "input"))
    )
    (net (code "54") (name "V_FOL_PWM") (class "Default")
      (node (ref "FOL_PWM") (pin "TP") (pinfunction "TP_TP") (pintype "input"))
      (node (ref "R10") (pin "2") (pinfunction "2_2") (pintype "passive"))
      (node (ref "U1") (pin "1") (pinfunction "PD3/OC2B/INT1/PTCXY_1") (pintype "bidirectional"))
    )
    (net (code "55") (name "unconnected-(U1A-AREF-Pad20)") (class "Default")
      (node (ref "U1") (pin "20") (pinfunction "AREF_20") (pintype "input"))
    )
    (net (code "56") (name "unconnected-(U1A-PB0{slash}ICP1{slash}CLKO{slash}PTCXY-Pad12)") (class "Default")
      (node (ref "U1") (pin "12") (pinfunction "PB0/ICP1/CLKO/PTCXY_12") (pintype "bidirectional"))
    )
    (net (code "57") (name "unconnected-(U1A-PC2{slash}ADC2{slash}PTCY-Pad25)") (class "Default")
      (node (ref "U1") (pin "25") (pinfunction "PC2/ADC2/PTCY_25") (pintype "bidirectional"))
    )
    (net (code "58") (name "unconnected-(U1A-PC3{slash}ADC3{slash}PTCY-Pad26)") (class "Default")
      (node (ref "U1") (pin "26") (pinfunction "PC3/ADC3/PTCY_26") (pintype "bidirectional"))
    )
    (net (code "59") (name "unconnected-(U1A-PC4{slash}ADC4{slash}PTCY{slash}SDA0-Pad27)") (class "Default")
      (node (ref "U1") (pin "27") (pinfunction "PC4/ADC4/PTCY/SDA0_27") (pintype "bidirectional"))
    )
    (net (code "60") (name "unconnected-(U1A-PC5{slash}ADC5{slash}PTCY{slash}SCL0-Pad28)") (class "Default")
      (node (ref "U1") (pin "28") (pinfunction "PC5/ADC5/PTCY/SCL0_28") (pintype "bidirectional"))
    )
    (net (code "61") (name "unconnected-(U1A-PE2{slash}ADC6{slash}PTCY{slash}ICP3{slash}~{SS1}-Pad19)") (class "Default")
      (node (ref "U1") (pin "19") (pinfunction "PE2/ADC6/PTCY/ICP3/~{SS1}_19") (pintype "bidirectional"))
    )
    (net (code "62") (name "unconnected-(U1A-PE3{slash}ADC7{slash}PTCY{slash}T3{slash}MOSI1-Pad22)") (class "Default")
      (node (ref "U1") (pin "22") (pinfunction "PE3/ADC7/PTCY/T3/MOSI1_22") (pintype "bidirectional"))
    )
  )
)
